# pc_max30205_brk.net
KiCad netlist of a schematic drawn in EAGLE
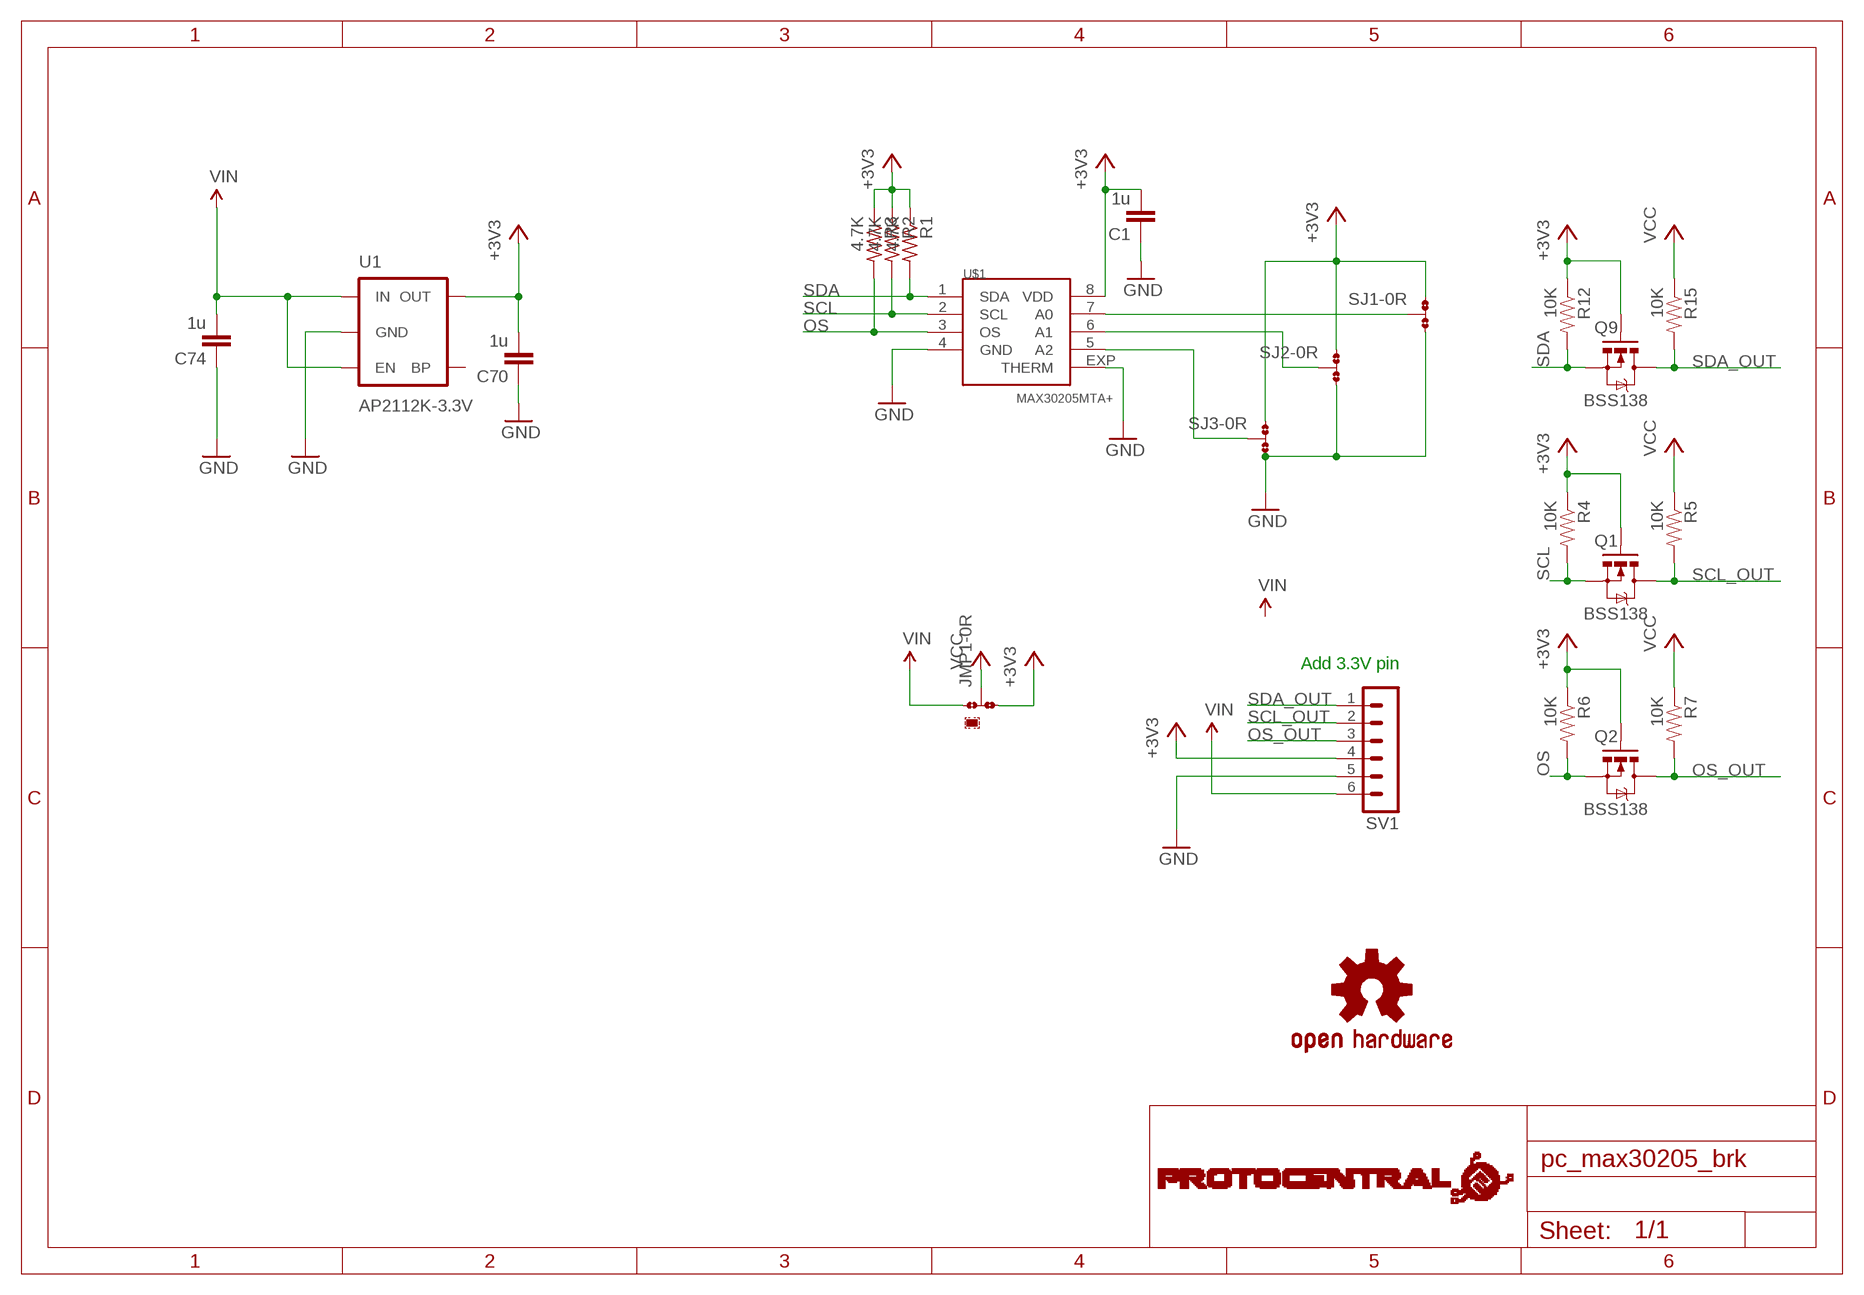
[diagram p0: schematic, sheet 1]

(export (version "E")
  (design (tool "Eeschema 10.0.6"))
  (components
    (comp (ref "C1")
      (value "1u")
      (footprint "eagle-import:C0805")
      (libsource (lib "eagle-import") (part "C-EUC0805"))
    )
    (comp (ref "C70")
      (value "1u")
      (footprint "eagle-import:C0805")
      (libsource (lib "eagle-import") (part "C-EUC0805"))
    )
    (comp (ref "C74")
      (value "1u")
      (footprint "eagle-import:C0805")
      (libsource (lib "eagle-import") (part "C-EUC0805"))
    )
    (comp (ref "JMP1")
      (value "0R-JUMPA")
      (footprint "eagle-import:A0R-JMP-0402")
      (libsource (lib "eagle-import") (part "0R-JUMPA"))
    )
    (comp (ref "Q1")
      (value "BSS138")
      (footprint "eagle-import:SOT23-3")
      (libsource (lib "eagle-import") (part "MOSFET-NCHANNELSMD"))
    )
    (comp (ref "Q2")
      (value "BSS138")
      (footprint "eagle-import:SOT23-3")
      (libsource (lib "eagle-import") (part "MOSFET-NCHANNELSMD"))
    )
    (comp (ref "Q9")
      (value "BSS138")
      (footprint "eagle-import:SOT23-3")
      (libsource (lib "eagle-import") (part "MOSFET-NCHANNELSMD"))
    )
    (comp (ref "R1")
      (value "4.7K")
      (footprint "eagle-import:R0402")
      (libsource (lib "eagle-import") (part "R-US_R0402"))
    )
    (comp (ref "R2")
      (value "4.7K")
      (footprint "eagle-import:R0402")
      (libsource (lib "eagle-import") (part "R-US_R0402"))
    )
    (comp (ref "R3")
      (value "4.7K")
      (footprint "eagle-import:R0402")
      (libsource (lib "eagle-import") (part "R-US_R0402"))
    )
    (comp (ref "R4")
      (value "10K")
      (footprint "eagle-import:0805")
      (libsource (lib "eagle-import") (part "RESISTOR0805-RES"))
    )
    (comp (ref "R5")
      (value "10K")
      (footprint "eagle-import:0805")
      (libsource (lib "eagle-import") (part "RESISTOR0805-RES"))
    )
    (comp (ref "R6")
      (value "10K")
      (footprint "eagle-import:0805")
      (libsource (lib "eagle-import") (part "RESISTOR0805-RES"))
    )
    (comp (ref "R7")
      (value "10K")
      (footprint "eagle-import:0805")
      (libsource (lib "eagle-import") (part "RESISTOR0805-RES"))
    )
    (comp (ref "R12")
      (value "10K")
      (footprint "eagle-import:0805")
      (libsource (lib "eagle-import") (part "RESISTOR0805-RES"))
    )
    (comp (ref "R15")
      (value "10K")
      (footprint "eagle-import:0805")
      (libsource (lib "eagle-import") (part "RESISTOR0805-RES"))
    )
    (comp (ref "SJ1")
      (value "0R-JUMPA")
      (footprint "eagle-import:A0R-JMP-0402")
      (libsource (lib "eagle-import") (part "0R-JUMPA"))
    )
    (comp (ref "SJ2")
      (value "0R-JUMPA")
      (footprint "eagle-import:A0R-JMP-0402")
      (libsource (lib "eagle-import") (part "0R-JUMPA"))
    )
    (comp (ref "SJ3")
      (value "0R-JUMPA")
      (footprint "eagle-import:A0R-JMP-0402")
      (libsource (lib "eagle-import") (part "0R-JUMPA"))
    )
    (comp (ref "SV1")
      (value "MA06-1")
      (footprint "eagle-import:MA06-1")
      (libsource (lib "eagle-import") (part "MA06-1"))
    )
    (comp (ref "U$1")
      (value "MAX30205MTA+")
      (footprint "eagle-import:TDFN-08")
      (libsource (lib "eagle-import") (part "MAX30205MTA+"))
    )
    (comp (ref "U$5")
      (value "PROTY-LOGO")
      (footprint "eagle-import:LOGO-PROTY")
      (libsource (lib "eagle-import") (part "PROTY-LOGO"))
    )
    (comp (ref "U$7")
      (value "OSHW-LOGOS")
      (footprint "eagle-import:OSHW-LOGO-S")
      (libsource (lib "eagle-import") (part "OSHW-LOGOS"))
    )
    (comp (ref "U1")
      (value "AP2112K-3.3V")
      (footprint "eagle-import:SOT23-5")
      (libsource (lib "eagle-import") (part "V_REG_LDOSMD"))
    )
  )
  (nets
    (net (code "1") (name "+3V3") (class "Default")
      (node (ref "C1") (pin "2") (pinfunction "2_2") (pintype "passive"))
      (node (ref "C70") (pin "2") (pinfunction "2_2") (pintype "passive"))
      (node (ref "JMP1") (pin "3") (pinfunction "3_3") (pintype "passive"))
      (node (ref "Q1") (pin "1") (pinfunction "G_1") (pintype "passive"))
      (node (ref "Q2") (pin "1") (pinfunction "G_1") (pintype "passive"))
      (node (ref "Q9") (pin "1") (pinfunction "G_1") (pintype "passive"))
      (node (ref "R1") (pin "1") (pinfunction "1_1") (pintype "passive"))
      (node (ref "R12") (pin "1") (pinfunction "1_1") (pintype "passive"))
      (node (ref "R2") (pin "1") (pinfunction "1_1") (pintype "passive"))
      (node (ref "R3") (pin "1") (pinfunction "1_1") (pintype "passive"))
      (node (ref "R4") (pin "1") (pinfunction "1_1") (pintype "passive"))
      (node (ref "R6") (pin "1") (pinfunction "1_1") (pintype "passive"))
      (node (ref "SJ1") (pin "1") (pinfunction "1_1") (pintype "passive"))
      (node (ref "SJ2") (pin "1") (pinfunction "1_1") (pintype "passive"))
      (node (ref "SJ3") (pin "1") (pinfunction "1_1") (pintype "passive"))
      (node (ref "SV1") (pin "4") (pinfunction "4_4") (pintype "passive"))
      (node (ref "U$1") (pin "8") (pinfunction "VDD_8") (pintype "bidirectional"))
      (node (ref "U1") (pin "5") (pinfunction "OUT_5") (pintype "passive"))
    )
    (net (code "2") (name "/OS") (class "Default")
      (node (ref "Q2") (pin "2") (pinfunction "S_2") (pintype "passive"))
      (node (ref "R3") (pin "2") (pinfunction "2_2") (pintype "passive"))
      (node (ref "R6") (pin "2") (pinfunction "2_2") (pintype "passive"))
      (node (ref "U$1") (pin "3") (pinfunction "OS_3") (pintype "bidirectional"))
    )
    (net (code "3") (name "/OS_OUT") (class "Default")
      (node (ref "Q2") (pin "3") (pinfunction "D_3") (pintype "passive"))
      (node (ref "R7") (pin "2") (pinfunction "2_2") (pintype "passive"))
      (node (ref "SV1") (pin "3") (pinfunction "3_3") (pintype "passive"))
    )
    (net (code "4") (name "/SCL") (class "Default")
      (node (ref "Q1") (pin "2") (pinfunction "S_2") (pintype "passive"))
      (node (ref "R2") (pin "2") (pinfunction "2_2") (pintype "passive"))
      (node (ref "R4") (pin "2") (pinfunction "2_2") (pintype "passive"))
      (node (ref "U$1") (pin "2") (pinfunction "SCL_2") (pintype "bidirectional"))
    )
    (net (code "5") (name "/SCL_OUT") (class "Default")
      (node (ref "Q1") (pin "3") (pinfunction "D_3") (pintype "passive"))
      (node (ref "R5") (pin "2") (pinfunction "2_2") (pintype "passive"))
      (node (ref "SV1") (pin "2") (pinfunction "2_2") (pintype "passive"))
    )
    (net (code "6") (name "/SDA") (class "Default")
      (node (ref "Q9") (pin "2") (pinfunction "S_2") (pintype "passive"))
      (node (ref "R1") (pin "2") (pinfunction "2_2") (pintype "passive"))
      (node (ref "R12") (pin "2") (pinfunction "2_2") (pintype "passive"))
      (node (ref "U$1") (pin "1") (pinfunction "SDA_1") (pintype "bidirectional"))
    )
    (net (code "7") (name "/SDA_OUT") (class "Default")
      (node (ref "Q9") (pin "3") (pinfunction "D_3") (pintype "passive"))
      (node (ref "R15") (pin "2") (pinfunction "2_2") (pintype "passive"))
      (node (ref "SV1") (pin "1") (pinfunction "1_1") (pintype "passive"))
    )
    (net (code "8") (name "GND") (class "Default")
      (node (ref "C1") (pin "1") (pinfunction "1_1") (pintype "passive"))
      (node (ref "C70") (pin "1") (pinfunction "1_1") (pintype "passive"))
      (node (ref "C74") (pin "1") (pinfunction "1_1") (pintype "passive"))
      (node (ref "SJ1") (pin "3") (pinfunction "3_3") (pintype "passive"))
      (node (ref "SJ2") (pin "3") (pinfunction "3_3") (pintype "passive"))
      (node (ref "SJ3") (pin "3") (pinfunction "3_3") (pintype "passive"))
      (node (ref "SV1") (pin "5") (pinfunction "5_5") (pintype "passive"))
      (node (ref "U$1") (pin "4") (pinfunction "GND_4") (pintype "bidirectional"))
      (node (ref "U$1") (pin "EXP") (pinfunction "THERM_EXP") (pintype "bidirectional"))
      (node (ref "U1") (pin "2") (pinfunction "GND_2") (pintype "input"))
    )
    (net (code "9") (name "Net-(U$1-A0)") (class "Default")
      (node (ref "SJ1") (pin "2") (pinfunction "2_2") (pintype "passive"))
      (node (ref "U$1") (pin "7") (pinfunction "A0_7") (pintype "bidirectional"))
    )
    (net (code "10") (name "Net-(U$1-A1)") (class "Default")
      (node (ref "SJ2") (pin "2") (pinfunction "2_2") (pintype "passive"))
      (node (ref "U$1") (pin "6") (pinfunction "A1_6") (pintype "bidirectional"))
    )
    (net (code "11") (name "Net-(U$1-A2)") (class "Default")
      (node (ref "SJ3") (pin "2") (pinfunction "2_2") (pintype "passive"))
      (node (ref "U$1") (pin "5") (pinfunction "A2_5") (pintype "bidirectional"))
    )
    (net (code "12") (name "VCC") (class "Default")
      (node (ref "JMP1") (pin "2") (pinfunction "2_2") (pintype "passive"))
      (node (ref "R15") (pin "1") (pinfunction "1_1") (pintype "passive"))
      (node (ref "R5") (pin "1") (pinfunction "1_1") (pintype "passive"))
      (node (ref "R7") (pin "1") (pinfunction "1_1") (pintype "passive"))
    )
    (net (code "13") (name "VIN") (class "Default")
      (node (ref "C74") (pin "2") (pinfunction "2_2") (pintype "passive"))
      (node (ref "JMP1") (pin "1") (pinfunction "1_1") (pintype "passive"))
      (node (ref "SV1") (pin "6") (pinfunction "6_6") (pintype "passive"))
      (node (ref "U1") (pin "1") (pinfunction "IN_1") (pintype "input"))
      (node (ref "U1") (pin "3") (pinfunction "EN_3") (pintype "input"))
    )
    (net (code "14") (name "unconnected-(U1-BP-Pad4)") (class "Default")
      (node (ref "U1") (pin "4") (pinfunction "BP_4") (pintype "input"))
    )
  )
)
